# wifi.net
KiCad netlist of a schematic drawn in Altium Designer
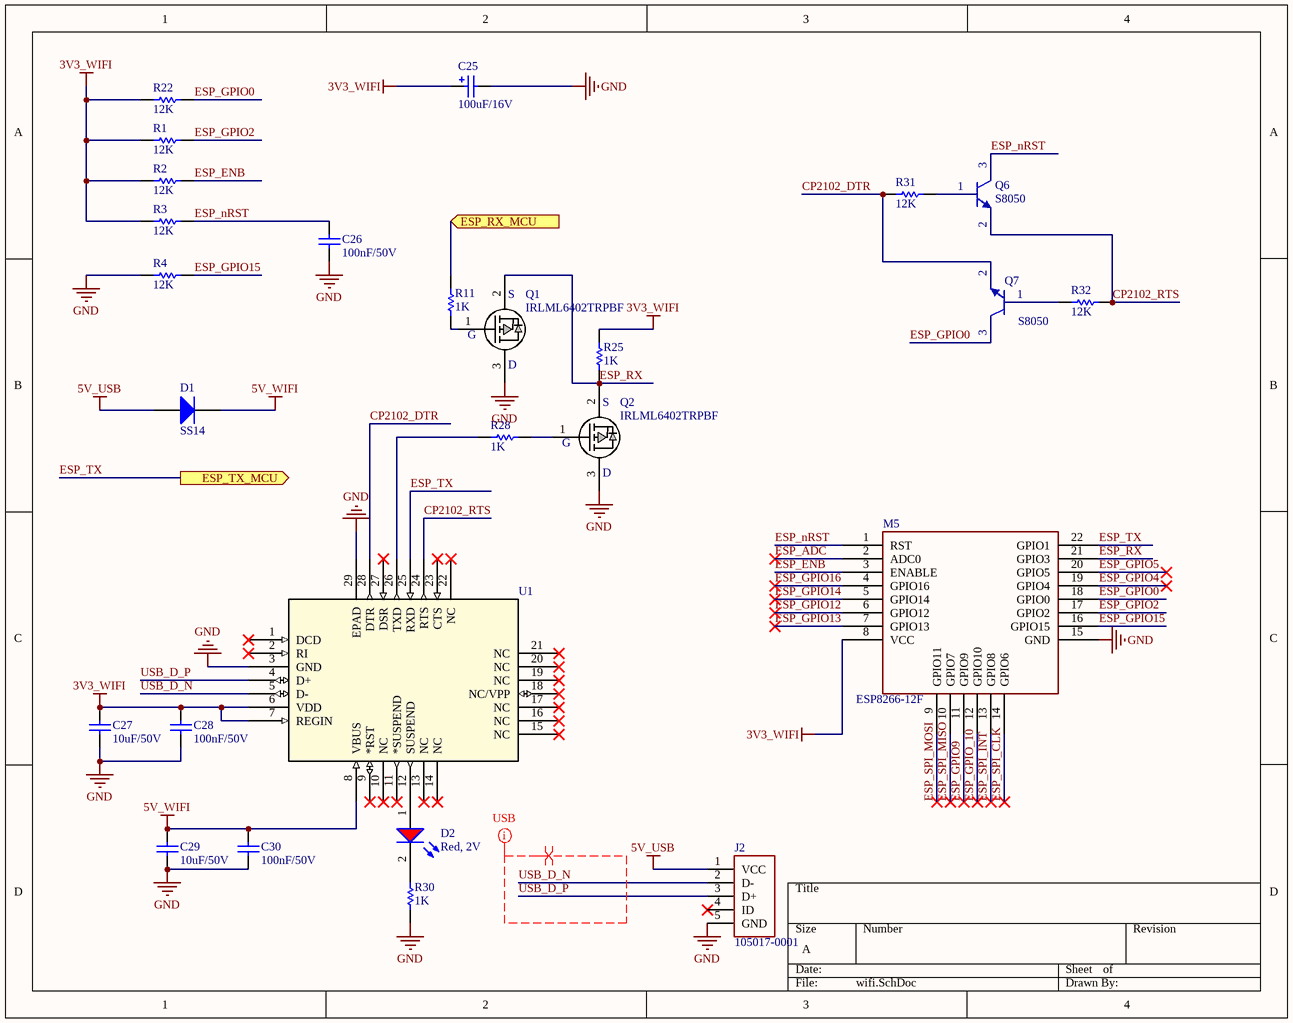
[diagram p0: wifi.SchDoc]

(export (version "E")
  (design (tool "Eeschema 10.0.6"))
  (components
    (comp (ref "C25")
      (value "100uF/16V")
      (footprint "Capacitor:CAP_SM_TAN")
      (fields
        (field (name "MANUFACTURER") "Nichicon")
        (field (name "MANUFACTURER PART NUMBER") "UWX1C101MCL1GB")
        (field (name "Comment") "TAJB107M006RNJ")
      )
      (libsource (lib "Capacitor") (part "Cap-Tan-100uF-16V"))
    )
    (comp (ref "C26")
      (value "100nF/50V")
      (footprint "CAP-SM-0805")
      (description "CAP CER 0.1UF 50V Y5V 0805")
      (fields
        (field (name "MANUFACTURER") "Samsung Electro-Mechanics")
        (field (name "MANUFACTURER PART NUMBER") "CL21F104ZBCNNNC")
      )
      (libsource (lib "Capacitor") (part "Cap-100nF-50V-0805"))
    )
    (comp (ref "C27")
      (value "10uF/50V")
      (footprint "CAP-SM-0805")
      (description "CAP CER 10UF 50V X5R 0805")
      (fields
        (field (name "MANUFACTURER") "Yageo")
        (field (name "MANUFACTURER PART NUMBER") "CC0805KKX5R9BB106")
      )
      (libsource (lib "Capacitor") (part "Cap-10uF-50V-0805"))
    )
    (comp (ref "C28")
      (value "100nF/50V")
      (footprint "CAP-SM-0805")
      (description "CAP CER 0.1UF 50V Y5V 0805")
      (fields
        (field (name "MANUFACTURER") "Samsung Electro-Mechanics")
        (field (name "MANUFACTURER PART NUMBER") "CL21F104ZBCNNNC")
      )
      (libsource (lib "Capacitor") (part "Cap-100nF-50V-0805"))
    )
    (comp (ref "C29")
      (value "10uF/50V")
      (footprint "CAP-SM-0805")
      (description "CAP CER 10UF 50V X5R 0805")
      (fields
        (field (name "MANUFACTURER") "Yageo")
        (field (name "MANUFACTURER PART NUMBER") "CC0805KKX5R9BB106")
      )
      (libsource (lib "Capacitor") (part "Cap-10uF-50V-0805"))
    )
    (comp (ref "C30")
      (value "100nF/50V")
      (footprint "CAP-SM-0805")
      (description "CAP CER 0.1UF 50V Y5V 0805")
      (fields
        (field (name "MANUFACTURER") "Samsung Electro-Mechanics")
        (field (name "MANUFACTURER PART NUMBER") "CL21F104ZBCNNNC")
      )
      (libsource (lib "Capacitor") (part "Cap-100nF-50V-0805"))
    )
    (comp (ref "D1")
      (value "SS14")
      (footprint "Diode:SS14")
      (description "DIODE SCHOTTKY 40V 1A SMA")
      (fields (field (name "MANUFACTURER") "ON Semiconductor"))
      (libsource (lib "Diode") (part "Diode-SS14"))
    )
    (comp (ref "D2")
      (value "Red, 2V")
      (footprint "LED_0805_Blue")
      (description "LED RED CLEAR T-1 T/H")
      (fields
        (field (name "MANUFACTURER") "Kingbright")
        (field (name "MANUFACTURER PART NUMBER") "WP710A10SEC/J3")
      )
      (libsource (lib "LED") (part "LED-RED-TH-3mm"))
    )
    (comp (ref "J2")
      (value "105017-0001")
      (footprint "Header-connector:CONN_105017-0001")
      (description "No Description Available")
      (fields (field (name "COPYRIGHT") "Copyright (C) 2018 Accelerated Designs. All rights reserved"))
      (libsource (lib "Header-Connector") (part "105017-0001"))
    )
    (comp (ref "M5")
      (value "ESP8266-12F")
      (footprint "ESP8266-12F")
      (fields (field (name "LOCAL SUPPLIER PART NUMBER") "HS000912"))
      (libsource (lib "PIF_robot") (part "ESP8266-12F"))
    )
    (comp (ref "Q1")
      (value "IRLML6402TRPBF")
      (footprint "MOSFET:SOT23_NEX")
      (description "P-Channel 20V 3.7A (Ta) 1.3W (Ta) Surface Mount Micro3™/SOT-23")
      (libsource (lib "MOSFET") (part "IRLML6402TRPBF"))
    )
    (comp (ref "Q2")
      (value "IRLML6402TRPBF")
      (footprint "MOSFET:SOT23_NEX")
      (description "P-Channel 20V 3.7A (Ta) 1.3W (Ta) Surface Mount Micro3™/SOT-23")
      (libsource (lib "MOSFET") (part "IRLML6402TRPBF"))
    )
    (comp (ref "Q6") (value "S8050") (footprint "BJT:SOT23_NEX") (libsource (lib "BJT") (part "S8050")))
    (comp (ref "Q7") (value "S8050") (footprint "BJT:SOT23_NEX") (libsource (lib "BJT") (part "S8050")))
    (comp (ref "R1")
      (value "12K")
      (footprint "Resistor:RES-SM-0805")
      (description "RES 12 KOHM JUMPER 0805")
      (fields
        (field (name "MANUFACTURER") "Vishay Thin Film")
        (field (name "MANUFACTURER PART NUMBER") "PAT0805E3121BST1")
      )
      (libsource (lib "Resistor") (part "Res-12K-0805"))
    )
    (comp (ref "R2")
      (value "12K")
      (footprint "Resistor:RES-SM-0805")
      (description "RES 12 KOHM JUMPER 0805")
      (fields
        (field (name "MANUFACTURER") "Vishay Thin Film")
        (field (name "MANUFACTURER PART NUMBER") "PAT0805E3121BST1")
      )
      (libsource (lib "Resistor") (part "Res-12K-0805"))
    )
    (comp (ref "R3")
      (value "12K")
      (footprint "Resistor:RES-SM-0805")
      (description "RES 12 KOHM JUMPER 0805")
      (fields
        (field (name "MANUFACTURER") "Vishay Thin Film")
        (field (name "MANUFACTURER PART NUMBER") "PAT0805E3121BST1")
      )
      (libsource (lib "Resistor") (part "Res-12K-0805"))
    )
    (comp (ref "R4")
      (value "12K")
      (footprint "Resistor:RES-SM-0805")
      (description "RES 12 KOHM JUMPER 0805")
      (fields
        (field (name "MANUFACTURER") "Vishay Thin Film")
        (field (name "MANUFACTURER PART NUMBER") "PAT0805E3121BST1")
      )
      (libsource (lib "Resistor") (part "Res-12K-0805"))
    )
    (comp (ref "R11")
      (value "1K")
      (footprint "Resistor:RES-SM-0805")
      (description "RES 1K OHM 1% 1/4W 0805")
      (fields
        (field (name "MANUFACTURER") "Stackpole Electronics Inc")
        (field (name "MANUFACTURER PART NUMBER") "RNCP0805FTD1K00")
      )
      (libsource (lib "Resistor") (part "Res-1K-0805"))
    )
    (comp (ref "R22")
      (value "12K")
      (footprint "Resistor:RES-SM-0805")
      (description "RES 12 KOHM JUMPER 0805")
      (fields
        (field (name "MANUFACTURER") "Vishay Thin Film")
        (field (name "MANUFACTURER PART NUMBER") "PAT0805E3121BST1")
      )
      (libsource (lib "Resistor") (part "Res-12K-0805"))
    )
    (comp (ref "R25")
      (value "1K")
      (footprint "Resistor:RES-SM-0805")
      (description "RES 1K OHM 1% 1/4W 0805")
      (fields
        (field (name "MANUFACTURER") "Stackpole Electronics Inc")
        (field (name "MANUFACTURER PART NUMBER") "RNCP0805FTD1K00")
      )
      (libsource (lib "Resistor") (part "Res-1K-0805"))
    )
    (comp (ref "R28")
      (value "1K")
      (footprint "Resistor:RES-SM-0805")
      (description "RES 1K OHM 1% 1/4W 0805")
      (fields
        (field (name "MANUFACTURER") "Stackpole Electronics Inc")
        (field (name "MANUFACTURER PART NUMBER") "RNCP0805FTD1K00")
      )
      (libsource (lib "Resistor") (part "Res-1K-0805"))
    )
    (comp (ref "R30")
      (value "1K")
      (footprint "Resistor:RES-SM-0805")
      (description "RES 1K OHM 1% 1/4W 0805")
      (fields
        (field (name "MANUFACTURER") "Stackpole Electronics Inc")
        (field (name "MANUFACTURER PART NUMBER") "RNCP0805FTD1K00")
      )
      (libsource (lib "Resistor") (part "Res-1K-0805"))
    )
    (comp (ref "R31")
      (value "12K")
      (footprint "Resistor:RES-SM-0805")
      (description "RES 12 KOHM JUMPER 0805")
      (fields
        (field (name "MANUFACTURER") "Vishay Thin Film")
        (field (name "MANUFACTURER PART NUMBER") "PAT0805E3121BST1")
      )
      (libsource (lib "Resistor") (part "Res-12K-0805"))
    )
    (comp (ref "R32")
      (value "12K")
      (footprint "Resistor:RES-SM-0805")
      (description "RES 12 KOHM JUMPER 0805")
      (fields
        (field (name "MANUFACTURER") "Vishay Thin Film")
        (field (name "MANUFACTURER PART NUMBER") "PAT0805E3121BST1")
      )
      (libsource (lib "Resistor") (part "Res-12K-0805"))
    )
    (comp (ref "U1")
      (value "~")
      (footprint "CP2102-GM")
      (description "No Description Available")
      (fields
        (field (name "MANUFACTURER_PART_NUMBER") "CP2102-GM")
        (field (name "COPYRIGHT") "Copyright (C) 2018 Accelerated Designs. All rights reserved")
      )
      (libsource (lib "2020-06-18_11-57-54") (part "CP2102-GM"))
    )
  )
  (nets
    (net (code "1") (name "/CP2102_DTR") (class "Default")
      (node (ref "Q7") (pin "2") (pinfunction "E_2") (pintype "passive"))
      (node (ref "R31") (pin "1") (pinfunction "1_1") (pintype "passive"))
      (node (ref "U1") (pin "28") (pinfunction "DTR_28") (pintype "output"))
    )
    (net (code "2") (name "/CP2102_RTS") (class "Default")
      (node (ref "Q6") (pin "2") (pinfunction "E_2") (pintype "passive"))
      (node (ref "R32") (pin "2") (pinfunction "2_2") (pintype "passive"))
      (node (ref "U1") (pin "24") (pinfunction "RTS_24") (pintype "output"))
    )
    (net (code "3") (name "/ESP_ADC") (class "Default")
      (node (ref "M5") (pin "2") (pinfunction "ADC0_2") (pintype "passive+no_connect"))
    )
    (net (code "4") (name "/ESP_ENB") (class "Default")
      (node (ref "M5") (pin "3") (pinfunction "ENABLE_3") (pintype "passive"))
      (node (ref "R2") (pin "2") (pinfunction "2_2") (pintype "passive"))
    )
    (net (code "5") (name "/ESP_GPIO0") (class "Default")
      (node (ref "M5") (pin "18") (pinfunction "GPIO0_18") (pintype "passive"))
      (node (ref "Q7") (pin "3") (pinfunction "C_3") (pintype "passive"))
      (node (ref "R22") (pin "2") (pinfunction "2_2") (pintype "passive"))
    )
    (net (code "6") (name "/ESP_GPIO2") (class "Default")
      (node (ref "M5") (pin "17") (pinfunction "GPIO2_17") (pintype "passive"))
      (node (ref "R1") (pin "2") (pinfunction "2_2") (pintype "passive"))
    )
    (net (code "7") (name "/ESP_GPIO4") (class "Default")
      (node (ref "M5") (pin "19") (pinfunction "GPIO4_19") (pintype "passive+no_connect"))
    )
    (net (code "8") (name "/ESP_GPIO5") (class "Default")
      (node (ref "M5") (pin "20") (pinfunction "GPIO5_20") (pintype "passive+no_connect"))
    )
    (net (code "9") (name "/ESP_GPIO9") (class "Default")
      (node (ref "M5") (pin "11") (pinfunction "GPIO9_11") (pintype "passive+no_connect"))
    )
    (net (code "10") (name "/ESP_GPIO12") (class "Default")
      (node (ref "M5") (pin "6") (pinfunction "GPIO12_6") (pintype "passive+no_connect"))
    )
    (net (code "11") (name "/ESP_GPIO13") (class "Default")
      (node (ref "M5") (pin "7") (pinfunction "GPIO13_7") (pintype "passive+no_connect"))
    )
    (net (code "12") (name "/ESP_GPIO14") (class "Default")
      (node (ref "M5") (pin "5") (pinfunction "GPIO14_5") (pintype "passive+no_connect"))
    )
    (net (code "13") (name "/ESP_GPIO15") (class "Default")
      (node (ref "M5") (pin "16") (pinfunction "GPIO15_16") (pintype "passive"))
      (node (ref "R4") (pin "2") (pinfunction "2_2") (pintype "passive"))
    )
    (net (code "14") (name "/ESP_GPIO16") (class "Default")
      (node (ref "M5") (pin "4") (pinfunction "GPIO16_4") (pintype "passive+no_connect"))
    )
    (net (code "15") (name "/ESP_GPIO_10") (class "Default")
      (node (ref "M5") (pin "12") (pinfunction "GPIO10_12") (pintype "passive+no_connect"))
    )
    (net (code "16") (name "/ESP_RX") (class "Default")
      (node (ref "M5") (pin "21") (pinfunction "GPIO3_21") (pintype "passive"))
      (node (ref "Q1") (pin "2") (pinfunction "S_2") (pintype "passive"))
      (node (ref "Q2") (pin "2") (pinfunction "S_2") (pintype "passive"))
      (node (ref "R25") (pin "2") (pinfunction "2_2") (pintype "passive"))
    )
    (net (code "17") (name "/ESP_RX_MCU") (class "Default")
      (node (ref "R11") (pin "2") (pinfunction "2_2") (pintype "passive"))
    )
    (net (code "18") (name "/ESP_SPI_CLK") (class "Default")
      (node (ref "M5") (pin "14") (pinfunction "GPIO6_14") (pintype "passive+no_connect"))
    )
    (net (code "19") (name "/ESP_SPI_INT") (class "Default")
      (node (ref "M5") (pin "13") (pinfunction "GPIO8_13") (pintype "passive+no_connect"))
    )
    (net (code "20") (name "/ESP_SPI_MISO") (class "Default")
      (node (ref "M5") (pin "10") (pinfunction "GPIO7_10") (pintype "passive+no_connect"))
    )
    (net (code "21") (name "/ESP_SPI_MOSI") (class "Default")
      (node (ref "M5") (pin "9") (pinfunction "GPIO11_9") (pintype "passive+no_connect"))
    )
    (net (code "22") (name "/ESP_TX") (class "Default")
      (node (ref "M5") (pin "22") (pinfunction "GPIO1_22") (pintype "passive"))
      (node (ref "U1") (pin "25") (pinfunction "RXD_25") (pintype "input"))
    )
    (net (code "23") (name "/ESP_nRST") (class "Default")
      (node (ref "C26") (pin "2") (pinfunction "2_2") (pintype "passive"))
      (node (ref "M5") (pin "1") (pinfunction "RST_1") (pintype "passive"))
      (node (ref "Q6") (pin "3") (pinfunction "C_3") (pintype "passive"))
      (node (ref "R3") (pin "2") (pinfunction "2_2") (pintype "passive"))
    )
    (net (code "24") (name "/USB_D_N") (class "Default")
      (node (ref "J2") (pin "2") (pinfunction "D-_2") (pintype "passive"))
      (node (ref "U1") (pin "5") (pinfunction "D-_5") (pintype "bidirectional"))
    )
    (net (code "25") (name "/USB_D_P") (class "Default")
      (node (ref "J2") (pin "3") (pinfunction "D+_3") (pintype "passive"))
      (node (ref "U1") (pin "4") (pinfunction "D+_4") (pintype "bidirectional"))
    )
    (net (code "26") (name "3V3_WIFI") (class "Default")
      (node (ref "C25") (pin "1") (pinfunction "1_1") (pintype "passive"))
      (node (ref "C27") (pin "2") (pinfunction "2_2") (pintype "passive"))
      (node (ref "C28") (pin "2") (pinfunction "2_2") (pintype "passive"))
      (node (ref "M5") (pin "8") (pinfunction "VCC_8") (pintype "passive"))
      (node (ref "R1") (pin "1") (pinfunction "1_1") (pintype "passive"))
      (node (ref "R2") (pin "1") (pinfunction "1_1") (pintype "passive"))
      (node (ref "R22") (pin "1") (pinfunction "1_1") (pintype "passive"))
      (node (ref "R25") (pin "1") (pinfunction "1_1") (pintype "passive"))
      (node (ref "R3") (pin "1") (pinfunction "1_1") (pintype "passive"))
      (node (ref "U1") (pin "6") (pinfunction "VDD_6") (pintype "power_in"))
      (node (ref "U1") (pin "7") (pinfunction "REGIN_7") (pintype "input"))
    )
    (net (code "27") (name "5V_USB") (class "Default")
      (node (ref "D1") (pin "2") (pinfunction "A_2") (pintype "passive"))
      (node (ref "J2") (pin "1") (pinfunction "VCC_1") (pintype "passive"))
    )
    (net (code "28") (name "5V_WIFI") (class "Default")
      (node (ref "C29") (pin "2") (pinfunction "2_2") (pintype "passive"))
      (node (ref "C30") (pin "2") (pinfunction "2_2") (pintype "passive"))
      (node (ref "D1") (pin "1") (pinfunction "K_1") (pintype "passive"))
      (node (ref "U1") (pin "8") (pinfunction "VBUS_8") (pintype "input"))
    )
    (net (code "29") (name "GND") (class "Default")
      (node (ref "C25") (pin "2") (pinfunction "2_2") (pintype "passive"))
      (node (ref "C26") (pin "1") (pinfunction "1_1") (pintype "passive"))
      (node (ref "C27") (pin "1") (pinfunction "1_1") (pintype "passive"))
      (node (ref "C28") (pin "1") (pinfunction "1_1") (pintype "passive"))
      (node (ref "C29") (pin "1") (pinfunction "1_1") (pintype "passive"))
      (node (ref "C30") (pin "1") (pinfunction "1_1") (pintype "passive"))
      (node (ref "J2") (pin "5") (pinfunction "GND_5") (pintype "passive"))
      (node (ref "M5") (pin "15") (pinfunction "GND_15") (pintype "passive"))
      (node (ref "Q1") (pin "3") (pinfunction "D_3") (pintype "passive"))
      (node (ref "Q2") (pin "3") (pinfunction "D_3") (pintype "passive"))
      (node (ref "R30") (pin "1") (pinfunction "1_1") (pintype "passive"))
      (node (ref "R4") (pin "1") (pinfunction "1_1") (pintype "passive"))
      (node (ref "U1") (pin "29") (pinfunction "EPAD_29") (pintype "passive"))
      (node (ref "U1") (pin "3") (pinfunction "GND_3") (pintype "power_in"))
    )
    (net (code "30") (name "Net-(D2-A)") (class "Default")
      (node (ref "D2") (pin "1") (pinfunction "A_1") (pintype "passive"))
      (node (ref "U1") (pin "12") (pinfunction "SUSPEND_12") (pintype "output"))
    )
    (net (code "31") (name "Net-(D2-K)") (class "Default")
      (node (ref "D2") (pin "2") (pinfunction "K_2") (pintype "passive"))
      (node (ref "R30") (pin "2") (pinfunction "2_2") (pintype "passive"))
    )
    (net (code "32") (name "Net-(Q1-G)") (class "Default")
      (node (ref "Q1") (pin "1") (pinfunction "G_1") (pintype "passive"))
      (node (ref "R11") (pin "1") (pinfunction "1_1") (pintype "passive"))
    )
    (net (code "33") (name "Net-(Q2-G)") (class "Default")
      (node (ref "Q2") (pin "1") (pinfunction "G_1") (pintype "passive"))
      (node (ref "R28") (pin "2") (pinfunction "2_2") (pintype "passive"))
    )
    (net (code "34") (name "Net-(Q6-B)") (class "Default")
      (node (ref "Q6") (pin "1") (pinfunction "B_1") (pintype "passive"))
      (node (ref "R31") (pin "2") (pinfunction "2_2") (pintype "passive"))
    )
    (net (code "35") (name "Net-(Q7-B)") (class "Default")
      (node (ref "Q7") (pin "1") (pinfunction "B_1") (pintype "passive"))
      (node (ref "R32") (pin "1") (pinfunction "1_1") (pintype "passive"))
    )
    (net (code "36") (name "Net-(U1-TXD)") (class "Default")
      (node (ref "R28") (pin "1") (pinfunction "1_1") (pintype "passive"))
      (node (ref "U1") (pin "26") (pinfunction "TXD_26") (pintype "output"))
    )
    (net (code "37") (name "unconnected-(J2-ID-Pad4)") (class "Default")
      (node (ref "J2") (pin "4") (pinfunction "ID_4") (pintype "passive+no_connect"))
    )
    (net (code "38") (name "unconnected-(U1-*RST-Pad9)") (class "Default")
      (node (ref "U1") (pin "9") (pinfunction "*RST_9") (pintype "bidirectional+no_connect"))
    )
    (net (code "39") (name "unconnected-(U1-*SUSPEND-Pad11)") (class "Default")
      (node (ref "U1") (pin "11") (pinfunction "*SUSPEND_11") (pintype "output+no_connect"))
    )
    (net (code "40") (name "unconnected-(U1-CTS-Pad23)") (class "Default")
      (node (ref "U1") (pin "23") (pinfunction "CTS_23") (pintype "input+no_connect"))
    )
    (net (code "41") (name "unconnected-(U1-DCD-Pad1)") (class "Default")
      (node (ref "U1") (pin "1") (pinfunction "DCD_1") (pintype "input+no_connect"))
    )
    (net (code "42") (name "unconnected-(U1-DSR-Pad27)") (class "Default")
      (node (ref "U1") (pin "27") (pinfunction "DSR_27") (pintype "input+no_connect"))
    )
    (net (code "43") (name "unconnected-(U1-NC-Pad10)") (class "Default")
      (node (ref "U1") (pin "10") (pinfunction "NC_10") (pintype "passive+no_connect"))
    )
    (net (code "44") (name "unconnected-(U1-NC-Pad13)") (class "Default")
      (node (ref "U1") (pin "13") (pinfunction "NC_13") (pintype "passive+no_connect"))
    )
    (net (code "45") (name "unconnected-(U1-NC-Pad14)") (class "Default")
      (node (ref "U1") (pin "14") (pinfunction "NC_14") (pintype "passive+no_connect"))
    )
    (net (code "46") (name "unconnected-(U1-NC-Pad15)") (class "Default")
      (node (ref "U1") (pin "15") (pinfunction "NC_15") (pintype "passive+no_connect"))
    )
    (net (code "47") (name "unconnected-(U1-NC-Pad16)") (class "Default")
      (node (ref "U1") (pin "16") (pinfunction "NC_16") (pintype "passive+no_connect"))
    )
    (net (code "48") (name "unconnected-(U1-NC-Pad17)") (class "Default")
      (node (ref "U1") (pin "17") (pinfunction "NC_17") (pintype "passive+no_connect"))
    )
    (net (code "49") (name "unconnected-(U1-NC-Pad19)") (class "Default")
      (node (ref "U1") (pin "19") (pinfunction "NC_19") (pintype "passive+no_connect"))
    )
    (net (code "50") (name "unconnected-(U1-NC-Pad20)") (class "Default")
      (node (ref "U1") (pin "20") (pinfunction "NC_20") (pintype "passive+no_connect"))
    )
    (net (code "51") (name "unconnected-(U1-NC-Pad21)") (class "Default")
      (node (ref "U1") (pin "21") (pinfunction "NC_21") (pintype "passive+no_connect"))
    )
    (net (code "52") (name "unconnected-(U1-NC-Pad22)") (class "Default")
      (node (ref "U1") (pin "22") (pinfunction "NC_22") (pintype "passive+no_connect"))
    )
    (net (code "53") (name "unconnected-(U1-NC{slash}VPP-Pad18)") (class "Default")
      (node (ref "U1") (pin "18") (pinfunction "NC/VPP_18") (pintype "bidirectional+no_connect"))
    )
    (net (code "54") (name "unconnected-(U1-RI-Pad2)") (class "Default")
      (node (ref "U1") (pin "2") (pinfunction "RI_2") (pintype "input+no_connect"))
    )
  )
)
